# I2C_Serial_ID.net
KiCad netlist of a schematic drawn in Altium Designer
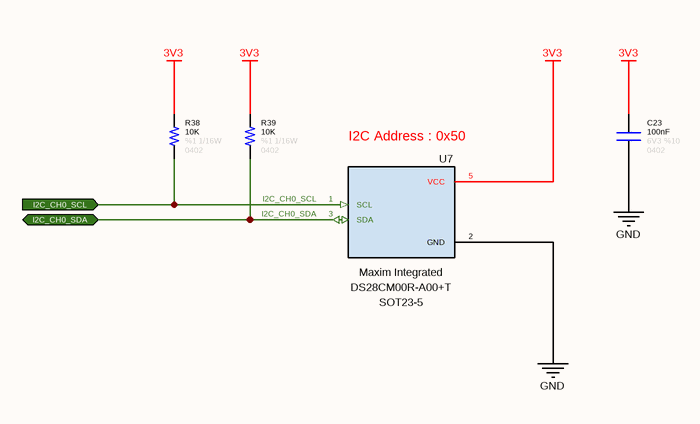
[diagram p0: I2C Serial ID.SchDoc]

(export (version "E")
  (design (tool "Eeschema 10.0.6"))
  (components
    (comp (ref "C23")
      (value "100nF")
      (footprint "CAPACITOR_0402")
      (description "Capacitor - 100nF [0402-6V3] (Ceramic)")
      (fields
        (field (name "MANUFACTURER PART NUMBER") "04026D104KAT4A")
        (field (name "TOLERANCE") "%10")
        (field (name "VOLTAGE") "6V3")
        (field (name "CASE") "0402")
        (field (name "Comment") "Capacitor - 100nF [0402] (Ceramic)")
      )
      (libsource (lib "Akkoyun") (part "Capacitor - 100nF [0402-6V3]"))
    )
    (comp (ref "R38")
      (value "10K")
      (footprint "RESISTOR_0402")
      (description "Thick Film Resistors - SMD 1/16 W 10 KOhm 1%")
      (fields
        (field (name "MANUFACTURER PART NUMBER") "CRCW040210K0FKED")
        (field (name "TOLERANCE") "%1")
        (field (name "CASE") "0402")
        (field (name "POWER") "1/16W")
        (field (name "Comment") "10K - 0402 - %1 - 1/16W")
      )
      (libsource (lib "Akkoyun") (part "Resistor - 10K [0402]"))
    )
    (comp (ref "R39")
      (value "10K")
      (footprint "RESISTOR_0402")
      (description "Thick Film Resistors - SMD 1/16 W 10 KOhm 1%")
      (fields
        (field (name "MANUFACTURER PART NUMBER") "CRCW040210K0FKED")
        (field (name "TOLERANCE") "%1")
        (field (name "CASE") "0402")
        (field (name "POWER") "1/16W")
        (field (name "Comment") "10K - 0402 - %1 - 1/16W")
      )
      (libsource (lib "Akkoyun") (part "Resistor - 10K [0402]"))
    )
    (comp (ref "U7")
      (value "DS28CM00R-A00+T")
      (footprint "SOT-23-5")
      (description "Security ICs / Authentication ICs I C/SMBus Silicon Serial Number")
      (fields
        (field (name "MANUFACTURER NAME") "Maxim Integrated")
        (field (name "MANUFACTURER PART NUMBER") "DS28CM00R-A00+T")
        (field (name "CASE") "SOT23-5")
      )
      (libsource (lib "Akkoyun") (part "IC - DS28C"))
    )
  )
  (nets
    (net (code "1") (name "/I2C_CH0_SCL") (class "Default")
      (node (ref "R38") (pin "1") (pinfunction "1_1") (pintype "passive"))
      (node (ref "U7") (pin "1") (pinfunction "SCL_1") (pintype "input"))
    )
    (net (code "2") (name "/I2C_CH0_SDA") (class "Default")
      (node (ref "R39") (pin "1") (pinfunction "1_1") (pintype "passive"))
      (node (ref "U7") (pin "3") (pinfunction "SDA_3") (pintype "bidirectional"))
    )
    (net (code "3") (name "3V3") (class "Default")
      (node (ref "C23") (pin "2") (pinfunction "2_2") (pintype "passive"))
      (node (ref "R38") (pin "2") (pinfunction "2_2") (pintype "passive"))
      (node (ref "R39") (pin "2") (pinfunction "2_2") (pintype "passive"))
      (node (ref "U7") (pin "5") (pinfunction "VCC_5") (pintype "power_in"))
    )
    (net (code "4") (name "GND") (class "Default")
      (node (ref "C23") (pin "1") (pinfunction "1_1") (pintype "passive"))
      (node (ref "U7") (pin "2") (pinfunction "GND_2") (pintype "passive"))
    )
    (net (code "5") (name "unconnected-(U7-NC-Pad4)") (class "Default")
      (node (ref "U7") (pin "4") (pinfunction "NC_4") (pintype "passive"))
    )
  )
)
